# ControllerDiagrams.net
KiCad netlist of a schematic drawn in Altium Designer
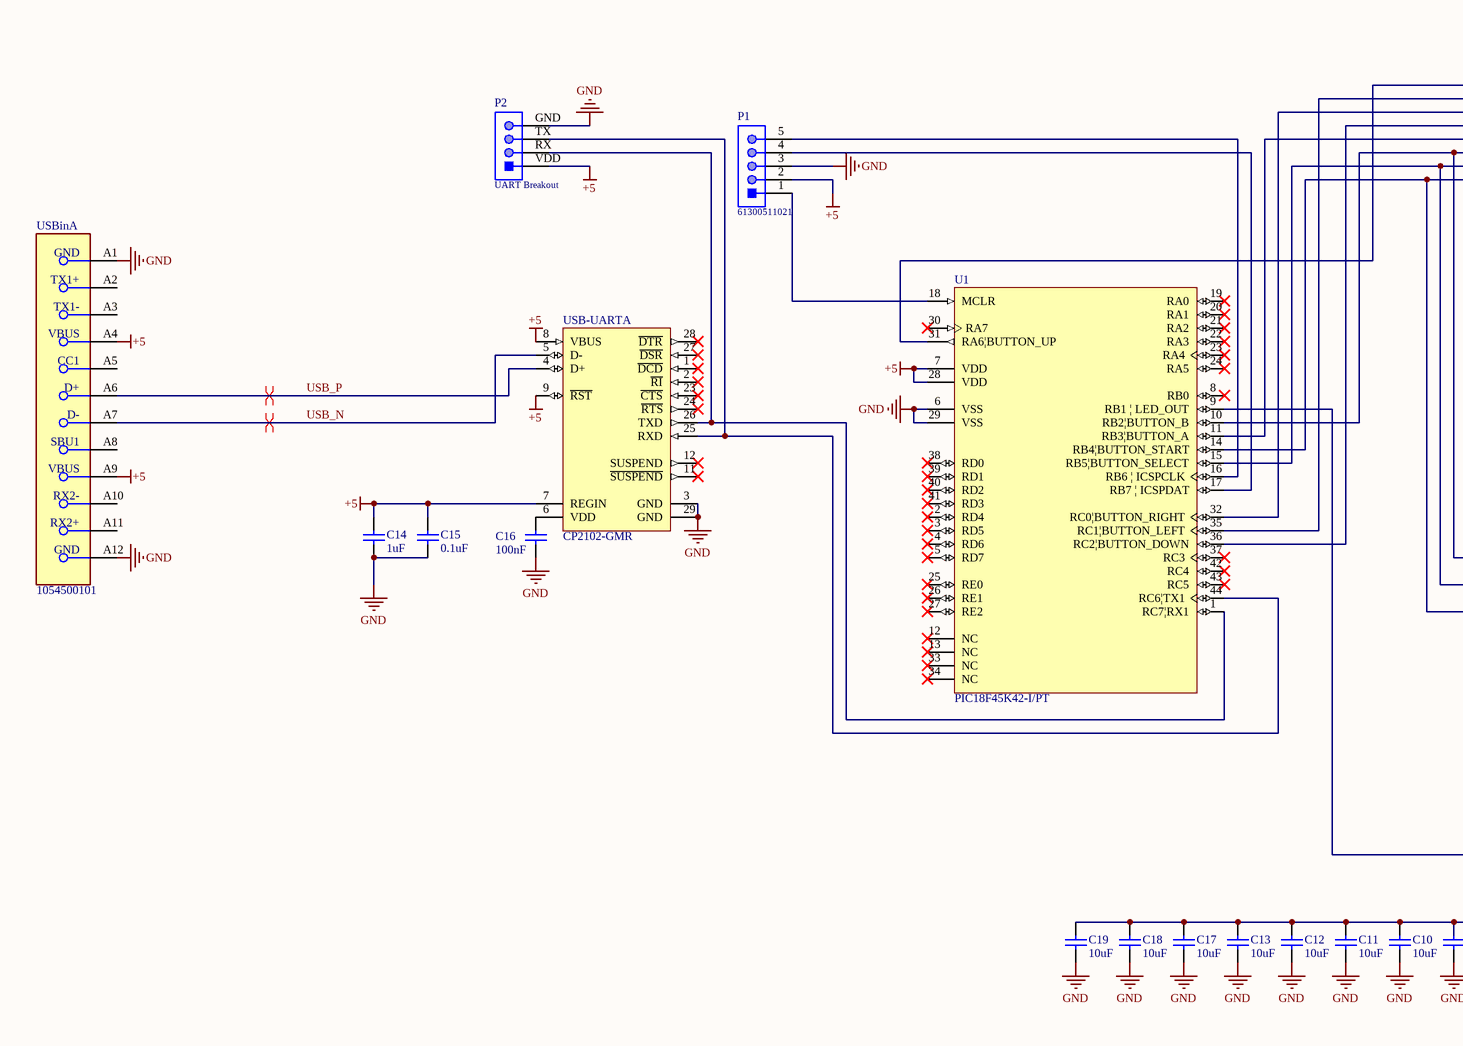
[diagram p0: ControllerDiagrams.SchDoc, left]
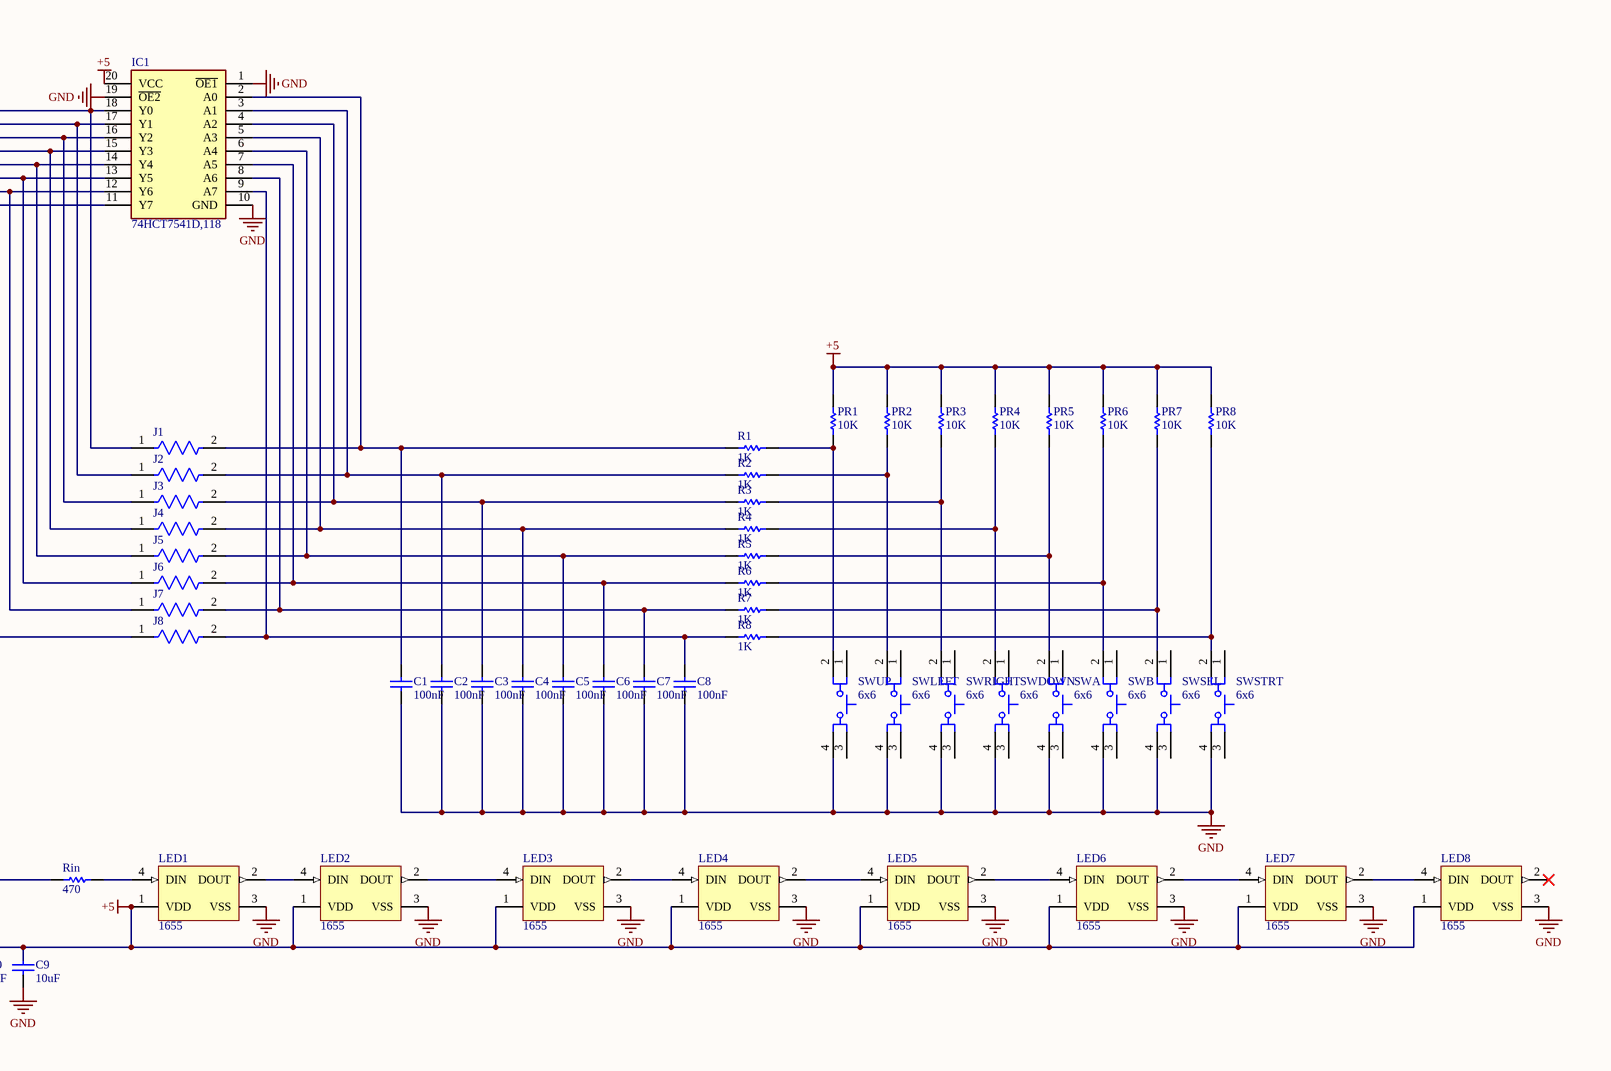
[diagram p1: ControllerDiagrams.SchDoc, right]

(export (version "E")
  (design (tool "Eeschema 10.0.6"))
  (components
    (comp (ref "C1")
      (value "100nF")
      (footprint "CAPC2013X140X50LL20T25")
      (description "Chip Capacitor, 2.2 uF, +/- 10%, 10 V, -55 to 85 degC, 0805 (2012 Metric), RoHS, Tape and Reel")
      (fields (field (name "MANUFACTURER") "AVX"))
      (libsource (lib "Altium Content Vault") (part "CAP-NP-2"))
    )
    (comp (ref "C2")
      (value "100nF")
      (footprint "CAPC2013X140X50LL20T25")
      (description "Chip Capacitor, 2.2 uF, +/- 10%, 10 V, -55 to 85 degC, 0805 (2012 Metric), RoHS, Tape and Reel")
      (fields (field (name "MANUFACTURER") "AVX"))
      (libsource (lib "Altium Content Vault") (part "CAP-NP-2"))
    )
    (comp (ref "C3")
      (value "100nF")
      (footprint "CAPC2013X140X50LL20T25")
      (description "Chip Capacitor, 2.2 uF, +/- 10%, 10 V, -55 to 85 degC, 0805 (2012 Metric), RoHS, Tape and Reel")
      (fields (field (name "MANUFACTURER") "AVX"))
      (libsource (lib "Altium Content Vault") (part "CAP-NP-2"))
    )
    (comp (ref "C4")
      (value "100nF")
      (footprint "CAPC2013X140X50LL20T25")
      (description "Chip Capacitor, 2.2 uF, +/- 10%, 10 V, -55 to 85 degC, 0805 (2012 Metric), RoHS, Tape and Reel")
      (fields (field (name "MANUFACTURER") "AVX"))
      (libsource (lib "Altium Content Vault") (part "CAP-NP-2"))
    )
    (comp (ref "C5")
      (value "100nF")
      (footprint "CAPC2013X140X50LL20T25")
      (description "Chip Capacitor, 2.2 uF, +/- 10%, 10 V, -55 to 85 degC, 0805 (2012 Metric), RoHS, Tape and Reel")
      (fields (field (name "MANUFACTURER") "AVX"))
      (libsource (lib "Altium Content Vault") (part "CAP-NP-2"))
    )
    (comp (ref "C6")
      (value "100nF")
      (footprint "CAPC2013X140X50LL20T25")
      (description "Chip Capacitor, 2.2 uF, +/- 10%, 10 V, -55 to 85 degC, 0805 (2012 Metric), RoHS, Tape and Reel")
      (fields (field (name "MANUFACTURER") "AVX"))
      (libsource (lib "Altium Content Vault") (part "CAP-NP-2"))
    )
    (comp (ref "C7")
      (value "100nF")
      (footprint "CAPC2013X140X50LL20T25")
      (description "Chip Capacitor, 2.2 uF, +/- 10%, 10 V, -55 to 85 degC, 0805 (2012 Metric), RoHS, Tape and Reel")
      (fields (field (name "MANUFACTURER") "AVX"))
      (libsource (lib "Altium Content Vault") (part "CAP-NP-2"))
    )
    (comp (ref "C8")
      (value "100nF")
      (footprint "CAPC2013X140X50LL20T25")
      (description "Chip Capacitor, 2.2 uF, +/- 10%, 10 V, -55 to 85 degC, 0805 (2012 Metric), RoHS, Tape and Reel")
      (fields (field (name "MANUFACTURER") "AVX"))
      (libsource (lib "Altium Content Vault") (part "CAP-NP-2"))
    )
    (comp (ref "C9")
      (value "10uF")
      (footprint "CAPC2013X140X50LL20T25")
      (description "Chip Capacitor, 2.2 uF, +/- 10%, 10 V, -55 to 85 degC, 0805 (2012 Metric), RoHS, Tape and Reel")
      (fields (field (name "MANUFACTURER") "AVX"))
      (libsource (lib "Altium Content Vault") (part "CAP-NP-2"))
    )
    (comp (ref "C10")
      (value "10uF")
      (footprint "CAPC2013X140X50LL20T25")
      (description "Chip Capacitor, 2.2 uF, +/- 10%, 10 V, -55 to 85 degC, 0805 (2012 Metric), RoHS, Tape and Reel")
      (fields (field (name "MANUFACTURER") "AVX"))
      (libsource (lib "Altium Content Vault") (part "CAP-NP-2"))
    )
    (comp (ref "C11")
      (value "10uF")
      (footprint "CAPC2013X140X50LL20T25")
      (description "Chip Capacitor, 2.2 uF, +/- 10%, 10 V, -55 to 85 degC, 0805 (2012 Metric), RoHS, Tape and Reel")
      (fields (field (name "MANUFACTURER") "AVX"))
      (libsource (lib "Altium Content Vault") (part "CAP-NP-2"))
    )
    (comp (ref "C12")
      (value "10uF")
      (footprint "CAPC2013X140X50LL20T25")
      (description "Chip Capacitor, 2.2 uF, +/- 10%, 10 V, -55 to 85 degC, 0805 (2012 Metric), RoHS, Tape and Reel")
      (fields (field (name "MANUFACTURER") "AVX"))
      (libsource (lib "Altium Content Vault") (part "CAP-NP-2"))
    )
    (comp (ref "C13")
      (value "10uF")
      (footprint "CAPC2013X140X50LL20T25")
      (description "Chip Capacitor, 2.2 uF, +/- 10%, 10 V, -55 to 85 degC, 0805 (2012 Metric), RoHS, Tape and Reel")
      (fields (field (name "MANUFACTURER") "AVX"))
      (libsource (lib "Altium Content Vault") (part "CAP-NP-2"))
    )
    (comp (ref "C14")
      (value "1uF")
      (footprint "CAPC2013X140X50LL20T25")
      (description "Chip Capacitor, 2.2 uF, +/- 10%, 10 V, -55 to 85 degC, 0805 (2012 Metric), RoHS, Tape and Reel")
      (fields (field (name "MANUFACTURER") "AVX"))
      (libsource (lib "Altium Content Vault") (part "CAP-NP-2"))
    )
    (comp (ref "C15")
      (value "0.1uF")
      (footprint "CAPC2013X140X50LL20T25")
      (description "Chip Capacitor, 2.2 uF, +/- 10%, 10 V, -55 to 85 degC, 0805 (2012 Metric), RoHS, Tape and Reel")
      (fields (field (name "MANUFACTURER") "AVX"))
      (libsource (lib "Altium Content Vault") (part "CAP-NP-2"))
    )
    (comp (ref "C16")
      (value "100nF")
      (footprint "CAPC2013X140X50LL20T25")
      (description "Chip Capacitor, 2.2 uF, +/- 10%, 10 V, -55 to 85 degC, 0805 (2012 Metric), RoHS, Tape and Reel")
      (fields (field (name "MANUFACTURER") "AVX"))
      (libsource (lib "Altium Content Vault") (part "CAP-NP-2"))
    )
    (comp (ref "C17")
      (value "10uF")
      (footprint "CAPC2013X140X50LL20T25")
      (description "Chip Capacitor, 2.2 uF, +/- 10%, 10 V, -55 to 85 degC, 0805 (2012 Metric), RoHS, Tape and Reel")
      (fields (field (name "MANUFACTURER") "AVX"))
      (libsource (lib "Altium Content Vault") (part "CAP-NP-2"))
    )
    (comp (ref "C18")
      (value "10uF")
      (footprint "CAPC2013X140X50LL20T25")
      (description "Chip Capacitor, 2.2 uF, +/- 10%, 10 V, -55 to 85 degC, 0805 (2012 Metric), RoHS, Tape and Reel")
      (fields (field (name "MANUFACTURER") "AVX"))
      (libsource (lib "Altium Content Vault") (part "CAP-NP-2"))
    )
    (comp (ref "C19")
      (value "10uF")
      (footprint "CAPC2013X140X50LL20T25")
      (description "Chip Capacitor, 2.2 uF, +/- 10%, 10 V, -55 to 85 degC, 0805 (2012 Metric), RoHS, Tape and Reel")
      (fields (field (name "MANUFACTURER") "AVX"))
      (libsource (lib "Altium Content Vault") (part "CAP-NP-2"))
    )
    (comp (ref "IC1")
      (value "74HCT7541D,118")
      (footprint "SamacSys:SOIC127P1032X265-20N")
      (description "Integrated Circuit")
      (fields (field (name "MOUSER PART NUMBER") "771-74HCT7541D-T"))
      (libsource (lib "*") (part "74HCT7541D,118"))
    )
    (comp (ref "J1")
      (value "~")
      (footprint "FP-ERJ-3GEY0R00V-MFG")
      (description "RES SMD 0 OHM JUMPER 1/10W 0603")
      (fields (field (name "TOLERANCE") "5%") (field (name "MANUFACTURER PART NUMBER") "ERJ-3GEY0R00V"))
      (libsource (lib "Altium Content Vault") (part "1029c3af85768c4190bb7ad29bc67b5"))
    )
    (comp (ref "J2")
      (value "~")
      (footprint "FP-ERJ-3GEY0R00V-MFG")
      (description "RES SMD 0 OHM JUMPER 1/10W 0603")
      (fields (field (name "TOLERANCE") "5%") (field (name "MANUFACTURER PART NUMBER") "ERJ-3GEY0R00V"))
      (libsource (lib "Altium Content Vault") (part "1029c3af85768c4190bb7ad29bc67b5"))
    )
    (comp (ref "J3")
      (value "~")
      (footprint "FP-ERJ-3GEY0R00V-MFG")
      (description "RES SMD 0 OHM JUMPER 1/10W 0603")
      (fields (field (name "TOLERANCE") "5%") (field (name "MANUFACTURER PART NUMBER") "ERJ-3GEY0R00V"))
      (libsource (lib "Altium Content Vault") (part "1029c3af85768c4190bb7ad29bc67b5"))
    )
    (comp (ref "J4")
      (value "~")
      (footprint "FP-ERJ-3GEY0R00V-MFG")
      (description "RES SMD 0 OHM JUMPER 1/10W 0603")
      (fields (field (name "TOLERANCE") "5%") (field (name "MANUFACTURER PART NUMBER") "ERJ-3GEY0R00V"))
      (libsource (lib "Altium Content Vault") (part "1029c3af85768c4190bb7ad29bc67b5"))
    )
    (comp (ref "J5")
      (value "~")
      (footprint "FP-ERJ-3GEY0R00V-MFG")
      (description "RES SMD 0 OHM JUMPER 1/10W 0603")
      (fields (field (name "TOLERANCE") "5%") (field (name "MANUFACTURER PART NUMBER") "ERJ-3GEY0R00V"))
      (libsource (lib "Altium Content Vault") (part "1029c3af85768c4190bb7ad29bc67b5"))
    )
    (comp (ref "J6")
      (value "~")
      (footprint "FP-ERJ-3GEY0R00V-MFG")
      (description "RES SMD 0 OHM JUMPER 1/10W 0603")
      (fields (field (name "TOLERANCE") "5%") (field (name "MANUFACTURER PART NUMBER") "ERJ-3GEY0R00V"))
      (libsource (lib "Altium Content Vault") (part "1029c3af85768c4190bb7ad29bc67b5"))
    )
    (comp (ref "J7")
      (value "~")
      (footprint "FP-ERJ-3GEY0R00V-MFG")
      (description "RES SMD 0 OHM JUMPER 1/10W 0603")
      (fields (field (name "TOLERANCE") "5%") (field (name "MANUFACTURER PART NUMBER") "ERJ-3GEY0R00V"))
      (libsource (lib "Altium Content Vault") (part "1029c3af85768c4190bb7ad29bc67b5"))
    )
    (comp (ref "J8")
      (value "~")
      (footprint "FP-ERJ-3GEY0R00V-MFG")
      (description "RES SMD 0 OHM JUMPER 1/10W 0603")
      (fields (field (name "TOLERANCE") "5%") (field (name "MANUFACTURER PART NUMBER") "ERJ-3GEY0R00V"))
      (libsource (lib "Altium Content Vault") (part "1029c3af85768c4190bb7ad29bc67b5"))
    )
    (comp (ref "LED1")
      (value "1655")
      (footprint "ADA-RGB-1655_V")
      (fields (field (name "MANUFACTURER") "Adafruit-Industries-LLC"))
      (libsource (lib "Altium Content Vault") (part "ADA-RGB-1655-4"))
    )
    (comp (ref "LED2")
      (value "1655")
      (footprint "ADA-RGB-1655_V")
      (fields (field (name "MANUFACTURER") "Adafruit-Industries-LLC"))
      (libsource (lib "Altium Content Vault") (part "ADA-RGB-1655-4"))
    )
    (comp (ref "LED3")
      (value "1655")
      (footprint "ADA-RGB-1655_V")
      (fields (field (name "MANUFACTURER") "Adafruit-Industries-LLC"))
      (libsource (lib "Altium Content Vault") (part "ADA-RGB-1655-4"))
    )
    (comp (ref "LED4")
      (value "1655")
      (footprint "ADA-RGB-1655_V")
      (fields (field (name "MANUFACTURER") "Adafruit-Industries-LLC"))
      (libsource (lib "Altium Content Vault") (part "ADA-RGB-1655-4"))
    )
    (comp (ref "LED5")
      (value "1655")
      (footprint "ADA-RGB-1655_V")
      (fields (field (name "MANUFACTURER") "Adafruit-Industries-LLC"))
      (libsource (lib "Altium Content Vault") (part "ADA-RGB-1655-4"))
    )
    (comp (ref "LED6")
      (value "1655")
      (footprint "ADA-RGB-1655_V")
      (fields (field (name "MANUFACTURER") "Adafruit-Industries-LLC"))
      (libsource (lib "Altium Content Vault") (part "ADA-RGB-1655-4"))
    )
    (comp (ref "LED7")
      (value "1655")
      (footprint "ADA-RGB-1655_V")
      (fields (field (name "MANUFACTURER") "Adafruit-Industries-LLC"))
      (libsource (lib "Altium Content Vault") (part "ADA-RGB-1655-4"))
    )
    (comp (ref "LED8")
      (value "1655")
      (footprint "ADA-RGB-1655_V")
      (fields (field (name "MANUFACTURER") "Adafruit-Industries-LLC"))
      (libsource (lib "Altium Content Vault") (part "ADA-RGB-1655-4"))
    )
    (comp (ref "P1")
      (value "61300511021")
      (footprint "61300511021")
      (description "THT Angled Pin Header WR-PHD, Pitch 2.54 mm, Single Row, 5 pins")
      (fields (field (name "MANUFACTURER") "Wurth Elektronik") (field (name "PUBLISHER") "WurthElektronik"))
      (libsource (lib "Altium Content Vault") (part "WE-CN-1P-M-R5"))
    )
    (comp (ref "P2")
      (value "UART Breakout")
      (footprint "61300411121")
      (description "THT Vertical Pin Header WR-PHD, Pitch 2.54 mm, Single Row, 4 pins")
      (fields
        (field (name "MANUFACTURER") "Wurth Elektronik")
        (field (name "PART NUMBER") "61300411121")
        (field (name "PUBLISHER") "WurthElektronik")
      )
      (libsource (lib "Altium Content Vault") (part "WE-CN-1P-M-R4"))
    )
    (comp (ref "PR1")
      (value "10K")
      (footprint "RESC2013X50X30LL20T20")
      (fields (field (name "MANUFACTURER") "Vishay Dale") (field (name "PART NUMBER") "CRCW08050000Z0EA"))
      (libsource (lib "Altium Content Vault") (part "RES"))
    )
    (comp (ref "PR2")
      (value "10K")
      (footprint "RESC2013X50X30LL20T20")
      (fields (field (name "MANUFACTURER") "Vishay Dale") (field (name "PART NUMBER") "CRCW08050000Z0EA"))
      (libsource (lib "Altium Content Vault") (part "RES"))
    )
    (comp (ref "PR3")
      (value "10K")
      (footprint "RESC2013X50X30LL20T20")
      (fields (field (name "MANUFACTURER") "Vishay Dale") (field (name "PART NUMBER") "CRCW08050000Z0EA"))
      (libsource (lib "Altium Content Vault") (part "RES"))
    )
    (comp (ref "PR4")
      (value "10K")
      (footprint "RESC2013X50X30LL20T20")
      (fields (field (name "MANUFACTURER") "Vishay Dale") (field (name "PART NUMBER") "CRCW08050000Z0EA"))
      (libsource (lib "Altium Content Vault") (part "RES"))
    )
    (comp (ref "PR5")
      (value "10K")
      (footprint "RESC2013X50X30LL20T20")
      (fields (field (name "MANUFACTURER") "Vishay Dale") (field (name "PART NUMBER") "CRCW08050000Z0EA"))
      (libsource (lib "Altium Content Vault") (part "RES"))
    )
    (comp (ref "PR6")
      (value "10K")
      (footprint "RESC2013X50X30LL20T20")
      (fields (field (name "MANUFACTURER") "Vishay Dale") (field (name "PART NUMBER") "CRCW08050000Z0EA"))
      (libsource (lib "Altium Content Vault") (part "RES"))
    )
    (comp (ref "PR7")
      (value "10K")
      (footprint "RESC2013X50X30LL20T20")
      (fields (field (name "MANUFACTURER") "Vishay Dale") (field (name "PART NUMBER") "CRCW08050000Z0EA"))
      (libsource (lib "Altium Content Vault") (part "RES"))
    )
    (comp (ref "PR8")
      (value "10K")
      (footprint "RESC2013X50X30LL20T20")
      (fields (field (name "MANUFACTURER") "Vishay Dale") (field (name "PART NUMBER") "CRCW08050000Z0EA"))
      (libsource (lib "Altium Content Vault") (part "RES"))
    )
    (comp (ref "R1")
      (value "1K")
      (footprint "RESC2013X50X30LL20T20")
      (fields (field (name "MANUFACTURER") "Vishay Dale") (field (name "PART NUMBER") "CRCW08050000Z0EA"))
      (libsource (lib "Altium Content Vault") (part "RES"))
    )
    (comp (ref "R2")
      (value "1K")
      (footprint "RESC2013X50X30LL20T20")
      (fields (field (name "MANUFACTURER") "Vishay Dale") (field (name "PART NUMBER") "CRCW08050000Z0EA"))
      (libsource (lib "Altium Content Vault") (part "RES"))
    )
    (comp (ref "R3")
      (value "1K")
      (footprint "RESC2013X50X30LL20T20")
      (fields (field (name "MANUFACTURER") "Vishay Dale") (field (name "PART NUMBER") "CRCW08050000Z0EA"))
      (libsource (lib "Altium Content Vault") (part "RES"))
    )
    (comp (ref "R4")
      (value "1K")
      (footprint "RESC2013X50X30LL20T20")
      (fields (field (name "MANUFACTURER") "Vishay Dale") (field (name "PART NUMBER") "CRCW08050000Z0EA"))
      (libsource (lib "Altium Content Vault") (part "RES"))
    )
    (comp (ref "R5")
      (value "1K")
      (footprint "RESC2013X50X30LL20T20")
      (fields (field (name "MANUFACTURER") "Vishay Dale") (field (name "PART NUMBER") "CRCW08050000Z0EA"))
      (libsource (lib "Altium Content Vault") (part "RES"))
    )
    (comp (ref "R6")
      (value "1K")
      (footprint "RESC2013X50X30LL20T20")
      (fields (field (name "MANUFACTURER") "Vishay Dale") (field (name "PART NUMBER") "CRCW08050000Z0EA"))
      (libsource (lib "Altium Content Vault") (part "RES"))
    )
    (comp (ref "R7")
      (value "1K")
      (footprint "RESC2013X50X30LL20T20")
      (fields (field (name "MANUFACTURER") "Vishay Dale") (field (name "PART NUMBER") "CRCW08050000Z0EA"))
      (libsource (lib "Altium Content Vault") (part "RES"))
    )
    (comp (ref "R8")
      (value "1K")
      (footprint "RESC2013X50X30LL20T20")
      (fields (field (name "MANUFACTURER") "Vishay Dale") (field (name "PART NUMBER") "CRCW08050000Z0EA"))
      (libsource (lib "Altium Content Vault") (part "RES"))
    )
    (comp (ref "Rin")
      (value "470")
      (footprint "RESC2013X50X30LL20T20")
      (fields (field (name "MANUFACTURER") "Vishay Dale") (field (name "PART NUMBER") "CRCW08050000Z0EA"))
      (libsource (lib "Altium Content Vault") (part "RES"))
    )
    (comp (ref "SWA")
      (value "6x6")
      (footprint "ESWI-TL1105SPF_V")
      (description "Tact Switch, SPST-NO, 50 mA, 12 VDC, -20 to 70 degC, 4-Pin THD, RoHS, Bulk")
      (fields (field (name "MANUFACTURER") "E-Switch"))
      (libsource (lib "Altium Content Vault") (part "SW-SPST-NO-4"))
    )
    (comp (ref "SWB")
      (value "6x6")
      (footprint "ESWI-TL1105SPF_V")
      (description "Tact Switch, SPST-NO, 50 mA, 12 VDC, -20 to 70 degC, 4-Pin THD, RoHS, Bulk")
      (fields (field (name "MANUFACTURER") "E-Switch"))
      (libsource (lib "Altium Content Vault") (part "SW-SPST-NO-4"))
    )
    (comp (ref "SWDOWN")
      (value "6x6")
      (footprint "ESWI-TL1105SPF_V")
      (description "Tact Switch, SPST-NO, 50 mA, 12 VDC, -20 to 70 degC, 4-Pin THD, RoHS, Bulk")
      (fields (field (name "MANUFACTURER") "E-Switch"))
      (libsource (lib "Altium Content Vault") (part "SW-SPST-NO-4"))
    )
    (comp (ref "SWLEFT")
      (value "6x6")
      (footprint "ESWI-TL1105SPF_V")
      (description "Tact Switch, SPST-NO, 50 mA, 12 VDC, -20 to 70 degC, 4-Pin THD, RoHS, Bulk")
      (fields (field (name "MANUFACTURER") "E-Switch"))
      (libsource (lib "Altium Content Vault") (part "SW-SPST-NO-4"))
    )
    (comp (ref "SWRIGHT")
      (value "6x6")
      (footprint "ESWI-TL1105SPF_V")
      (description "Tact Switch, SPST-NO, 50 mA, 12 VDC, -20 to 70 degC, 4-Pin THD, RoHS, Bulk")
      (fields (field (name "MANUFACTURER") "E-Switch"))
      (libsource (lib "Altium Content Vault") (part "SW-SPST-NO-4"))
    )
    (comp (ref "SWSEL")
      (value "6x6")
      (footprint "ESWI-TL1105SPF_V")
      (description "Tact Switch, SPST-NO, 50 mA, 12 VDC, -20 to 70 degC, 4-Pin THD, RoHS, Bulk")
      (fields (field (name "MANUFACTURER") "E-Switch"))
      (libsource (lib "Altium Content Vault") (part "SW-SPST-NO-4"))
    )
    (comp (ref "SWSTRT")
      (value "6x6")
      (footprint "ESWI-TL1105SPF_V")
      (description "Tact Switch, SPST-NO, 50 mA, 12 VDC, -20 to 70 degC, 4-Pin THD, RoHS, Bulk")
      (fields (field (name "MANUFACTURER") "E-Switch"))
      (libsource (lib "Altium Content Vault") (part "SW-SPST-NO-4"))
    )
    (comp (ref "SWUP")
      (value "6x6")
      (footprint "ESWI-TL1105SPF_V")
      (description "Tact Switch, SPST-NO, 50 mA, 12 VDC, -20 to 70 degC, 4-Pin THD, RoHS, Bulk")
      (fields (field (name "MANUFACTURER") "E-Switch"))
      (libsource (lib "Altium Content Vault") (part "SW-SPST-NO-4"))
    )
    (comp (ref "U1")
      (value "PIC18F45K42-I/PT")
      (footprint "TQFP-PT44_M")
      (libsource (lib "Altium Content Vault") (part "MC-8B-16F874A-SQ44B"))
    )
    (comp (ref "USB-UART")
      (value "CP2102-GMR")
      (footprint "SLAB-QFN-28-3125x3125TP_M")
      (description "Single-Chip USB to URAT Bridge, 3.3 V, -40 to 85 degC, 28-Pin QFN, RoHS, Tape and Reel")
      (fields (field (name "MANUFACTURER") "Silicon Labs"))
      (libsource (lib "Altium Content Vault") (part "SLAB-CP210X-QFN-28-29"))
    )
    (comp (ref "USBin")
      (value "1054500101")
      (footprint "FP-1054500101-MFG")
      (description "CONN RCP USB3.1 TYPEC 24P SMD RA")
      (fields
        (field (name "MANUFACTURER") "Molex")
        (field (name "OCTOPART") "https://octopart.com/105450-0101-molex-68082325")
      )
      (libsource (lib "Altium Content Vault") (part "9808b19ecaf079fb99eed69f0495cd0"))
    )
  )
  (nets
    (net (code "1") (name "+5") (class "Default")
      (node (ref "C10") (pin "2") (pinfunction "2_2") (pintype "passive"))
      (node (ref "C11") (pin "2") (pinfunction "2_2") (pintype "passive"))
      (node (ref "C12") (pin "2") (pinfunction "2_2") (pintype "passive"))
      (node (ref "C13") (pin "2") (pinfunction "2_2") (pintype "passive"))
      (node (ref "C14") (pin "2") (pinfunction "2_2") (pintype "passive"))
      (node (ref "C15") (pin "2") (pinfunction "2_2") (pintype "passive"))
      (node (ref "C17") (pin "2") (pinfunction "2_2") (pintype "passive"))
      (node (ref "C18") (pin "2") (pinfunction "2_2") (pintype "passive"))
      (node (ref "C19") (pin "2") (pinfunction "2_2") (pintype "passive"))
      (node (ref "C9") (pin "2") (pinfunction "2_2") (pintype "passive"))
      (node (ref "IC1") (pin "20") (pinfunction "VCC_20") (pintype "passive"))
      (node (ref "LED1") (pin "1") (pinfunction "VDD_1") (pintype "power_in"))
      (node (ref "LED2") (pin "1") (pinfunction "VDD_1") (pintype "power_in"))
      (node (ref "LED3") (pin "1") (pinfunction "VDD_1") (pintype "power_in"))
      (node (ref "LED4") (pin "1") (pinfunction "VDD_1") (pintype "power_in"))
      (node (ref "LED5") (pin "1") (pinfunction "VDD_1") (pintype "power_in"))
      (node (ref "LED6") (pin "1") (pinfunction "VDD_1") (pintype "power_in"))
      (node (ref "LED7") (pin "1") (pinfunction "VDD_1") (pintype "power_in"))
      (node (ref "LED8") (pin "1") (pinfunction "VDD_1") (pintype "power_in"))
      (node (ref "P1") (pin "2") (pinfunction "2_2") (pintype "passive"))
      (node (ref "P2") (pin "VDD") (pinfunction "1_VDD") (pintype "passive"))
      (node (ref "PR1") (pin "2") (pinfunction "2_2") (pintype "passive"))
      (node (ref "PR2") (pin "2") (pinfunction "2_2") (pintype "passive"))
      (node (ref "PR3") (pin "2") (pinfunction "2_2") (pintype "passive"))
      (node (ref "PR4") (pin "2") (pinfunction "2_2") (pintype "passive"))
      (node (ref "PR5") (pin "2") (pinfunction "2_2") (pintype "passive"))
      (node (ref "PR6") (pin "2") (pinfunction "2_2") (pintype "passive"))
      (node (ref "PR7") (pin "2") (pinfunction "2_2") (pintype "passive"))
      (node (ref "PR8") (pin "2") (pinfunction "2_2") (pintype "passive"))
      (node (ref "U1") (pin "28") (pinfunction "VDD_28") (pintype "power_in"))
      (node (ref "U1") (pin "7") (pinfunction "VDD_7") (pintype "power_in"))
      (node (ref "USB-UART") (pin "7") (pinfunction "REGIN_7") (pintype "power_in"))
      (node (ref "USB-UART") (pin "8") (pinfunction "VBUS_8") (pintype "input"))
      (node (ref "USB-UART") (pin "9") (pinfunction "~{RST}_9") (pintype "bidirectional"))
      (node (ref "USBin") (pin "A4") (pinfunction "VBUS_A4") (pintype "passive"))
      (node (ref "USBin") (pin "A9") (pinfunction "VBUS_A9") (pintype "passive"))
    )
    (net (code "2") (name "/USB_N") (class "Default")
      (node (ref "USB-UART") (pin "5") (pinfunction "D-_5") (pintype "bidirectional"))
      (node (ref "USBin") (pin "A7") (pinfunction "D-_A7") (pintype "passive"))
    )
    (net (code "3") (name "/USB_P") (class "Default")
      (node (ref "USB-UART") (pin "4") (pinfunction "D+_4") (pintype "bidirectional"))
      (node (ref "USBin") (pin "A6") (pinfunction "D+_A6") (pintype "passive"))
    )
    (net (code "4") (name "GND") (class "Default")
      (node (ref "C1") (pin "1") (pinfunction "1_1") (pintype "passive"))
      (node (ref "C10") (pin "1") (pinfunction "1_1") (pintype "passive"))
      (node (ref "C11") (pin "1") (pinfunction "1_1") (pintype "passive"))
      (node (ref "C12") (pin "1") (pinfunction "1_1") (pintype "passive"))
      (node (ref "C13") (pin "1") (pinfunction "1_1") (pintype "passive"))
      (node (ref "C14") (pin "1") (pinfunction "1_1") (pintype "passive"))
      (node (ref "C15") (pin "1") (pinfunction "1_1") (pintype "passive"))
      (node (ref "C16") (pin "2") (pinfunction "2_2") (pintype "passive"))
      (node (ref "C17") (pin "1") (pinfunction "1_1") (pintype "passive"))
      (node (ref "C18") (pin "1") (pinfunction "1_1") (pintype "passive"))
      (node (ref "C19") (pin "1") (pinfunction "1_1") (pintype "passive"))
      (node (ref "C2") (pin "1") (pinfunction "1_1") (pintype "passive"))
      (node (ref "C3") (pin "1") (pinfunction "1_1") (pintype "passive"))
      (node (ref "C4") (pin "1") (pinfunction "1_1") (pintype "passive"))
      (node (ref "C5") (pin "1") (pinfunction "1_1") (pintype "passive"))
      (node (ref "C6") (pin "1") (pinfunction "1_1") (pintype "passive"))
      (node (ref "C7") (pin "1") (pinfunction "1_1") (pintype "passive"))
      (node (ref "C8") (pin "1") (pinfunction "1_1") (pintype "passive"))
      (node (ref "C9") (pin "1") (pinfunction "1_1") (pintype "passive"))
      (node (ref "IC1") (pin "1") (pinfunction "~{OE1}_1") (pintype "passive"))
      (node (ref "IC1") (pin "10") (pinfunction "GND_10") (pintype "passive"))
      (node (ref "IC1") (pin "19") (pinfunction "~{OE2}_19") (pintype "passive"))
      (node (ref "LED1") (pin "3") (pinfunction "VSS_3") (pintype "power_in"))
      (node (ref "LED2") (pin "3") (pinfunction "VSS_3") (pintype "power_in"))
      (node (ref "LED3") (pin "3") (pinfunction "VSS_3") (pintype "power_in"))
      (node (ref "LED4") (pin "3") (pinfunction "VSS_3") (pintype "power_in"))
      (node (ref "LED5") (pin "3") (pinfunction "VSS_3") (pintype "power_in"))
      (node (ref "LED6") (pin "3") (pinfunction "VSS_3") (pintype "power_in"))
      (node (ref "LED7") (pin "3") (pinfunction "VSS_3") (pintype "power_in"))
      (node (ref "LED8") (pin "3") (pinfunction "VSS_3") (pintype "power_in"))
      (node (ref "P1") (pin "3") (pinfunction "3_3") (pintype "passive"))
      (node (ref "P2") (pin "GND") (pinfunction "4_GND") (pintype "passive"))
      (node (ref "SWA") (pin "4") (pinfunction "4_4") (pintype "passive"))
      (node (ref "SWB") (pin "4") (pinfunction "4_4") (pintype "passive"))
      (node (ref "SWDOWN") (pin "4") (pinfunction "4_4") (pintype "passive"))
      (node (ref "SWLEFT") (pin "4") (pinfunction "4_4") (pintype "passive"))
      (node (ref "SWRIGHT") (pin "4") (pinfunction "4_4") (pintype "passive"))
      (node (ref "SWSEL") (pin "4") (pinfunction "4_4") (pintype "passive"))
      (node (ref "SWSTRT") (pin "4") (pinfunction "4_4") (pintype "passive"))
      (node (ref "SWUP") (pin "4") (pinfunction "4_4") (pintype "passive"))
      (node (ref "U1") (pin "29") (pinfunction "VSS_29") (pintype "power_in"))
      (node (ref "U1") (pin "6") (pinfunction "VSS_6") (pintype "power_in"))
      (node (ref "USB-UART") (pin "29") (pinfunction "GND_29") (pintype "power_in"))
      (node (ref "USB-UART") (pin "3") (pinfunction "GND_3") (pintype "power_in"))
      (node (ref "USBin") (pin "A1") (pinfunction "GND_A1") (pintype "passive"))
      (node (ref "USBin") (pin "A12") (pinfunction "GND_A12") (pintype "passive"))
    )
    (net (code "5") (name "Net-(IC1-A0)") (class "Default")
      (node (ref "C1") (pin "2") (pinfunction "2_2") (pintype "passive"))
      (node (ref "IC1") (pin "2") (pinfunction "A0_2") (pintype "passive"))
      (node (ref "J1") (pin "2") (pinfunction "2_2") (pintype "passive"))
      (node (ref "R1") (pin "2") (pinfunction "2_2") (pintype "passive"))
    )
    (net (code "6") (name "Net-(IC1-A1)") (class "Default")
      (node (ref "C2") (pin "2") (pinfunction "2_2") (pintype "passive"))
      (node (ref "IC1") (pin "3") (pinfunction "A1_3") (pintype "passive"))
      (node (ref "J2") (pin "2") (pinfunction "2_2") (pintype "passive"))
      (node (ref "R2") (pin "2") (pinfunction "2_2") (pintype "passive"))
    )
    (net (code "7") (name "Net-(IC1-A2)") (class "Default")
      (node (ref "C3") (pin "2") (pinfunction "2_2") (pintype "passive"))
      (node (ref "IC1") (pin "4") (pinfunction "A2_4") (pintype "passive"))
      (node (ref "J3") (pin "2") (pinfunction "2_2") (pintype "passive"))
      (node (ref "R3") (pin "2") (pinfunction "2_2") (pintype "passive"))
    )
    (net (code "8") (name "Net-(IC1-A3)") (class "Default")
      (node (ref "C4") (pin "2") (pinfunction "2_2") (pintype "passive"))
      (node (ref "IC1") (pin "5") (pinfunction "A3_5") (pintype "passive"))
      (node (ref "J4") (pin "2") (pinfunction "2_2") (pintype "passive"))
      (node (ref "R4") (pin "2") (pinfunction "2_2") (pintype "passive"))
    )
    (net (code "9") (name "Net-(IC1-A4)") (class "Default")
      (node (ref "C5") (pin "2") (pinfunction "2_2") (pintype "passive"))
      (node (ref "IC1") (pin "6") (pinfunction "A4_6") (pintype "passive"))
      (node (ref "J5") (pin "2") (pinfunction "2_2") (pintype "passive"))
      (node (ref "R5") (pin "2") (pinfunction "2_2") (pintype "passive"))
    )
    (net (code "10") (name "Net-(IC1-A5)") (class "Default")
      (node (ref "C6") (pin "2") (pinfunction "2_2") (pintype "passive"))
      (node (ref "IC1") (pin "7") (pinfunction "A5_7") (pintype "passive"))
      (node (ref "J6") (pin "2") (pinfunction "2_2") (pintype "passive"))
      (node (ref "R6") (pin "2") (pinfunction "2_2") (pintype "passive"))
    )
    (net (code "11") (name "Net-(IC1-A6)") (class "Default")
      (node (ref "C7") (pin "2") (pinfunction "2_2") (pintype "passive"))
      (node (ref "IC1") (pin "8") (pinfunction "A6_8") (pintype "passive"))
      (node (ref "J7") (pin "2") (pinfunction "2_2") (pintype "passive"))
      (node (ref "R7") (pin "2") (pinfunction "2_2") (pintype "passive"))
    )
    (net (code "12") (name "Net-(IC1-A7)") (class "Default")
      (node (ref "C8") (pin "2") (pinfunction "2_2") (pintype "passive"))
      (node (ref "IC1") (pin "9") (pinfunction "A7_9") (pintype "passive"))
      (node (ref "J8") (pin "2") (pinfunction "2_2") (pintype "passive"))
      (node (ref "R8") (pin "2") (pinfunction "2_2") (pintype "passive"))
    )
    (net (code "13") (name "Net-(IC1-Y0)") (class "Default")
      (node (ref "IC1") (pin "18") (pinfunction "Y0_18") (pintype "passive"))
      (node (ref "J1") (pin "1") (pinfunction "1_1") (pintype "passive"))
      (node (ref "U1") (pin "31") (pinfunction "RA6¦BUTTON_UP_31") (pintype "output"))
    )
    (net (code "14") (name "Net-(IC1-Y1)") (class "Default")
      (node (ref "IC1") (pin "17") (pinfunction "Y1_17") (pintype "passive"))
      (node (ref "J2") (pin "1") (pinfunction "1_1") (pintype "passive"))
      (node (ref "U1") (pin "35") (pinfunction "RC1¦BUTTON_LEFT_35") (pintype "bidirectional"))
    )
    (net (code "15") (name "Net-(IC1-Y2)") (class "Default")
      (node (ref "IC1") (pin "16") (pinfunction "Y2_16") (pintype "passive"))
      (node (ref "J3") (pin "1") (pinfunction "1_1") (pintype "passive"))
      (node (ref "U1") (pin "32") (pinfunction "RC0¦BUTTON_RIGHT_32") (pintype "bidirectional"))
    )
    (net (code "16") (name "Net-(IC1-Y3)") (class "Default")
      (node (ref "IC1") (pin "15") (pinfunction "Y3_15") (pintype "passive"))
      (node (ref "J4") (pin "1") (pinfunction "1_1") (pintype "passive"))
      (node (ref "U1") (pin "36") (pinfunction "RC2¦BUTTON_DOWN_36") (pintype "bidirectional"))
    )
    (net (code "17") (name "Net-(IC1-Y4)") (class "Default")
      (node (ref "IC1") (pin "14") (pinfunction "Y4_14") (pintype "passive"))
      (node (ref "J5") (pin "1") (pinfunction "1_1") (pintype "passive"))
      (node (ref "U1") (pin "11") (pinfunction "RB3¦BUTTON_A_11") (pintype "bidirectional"))
    )
    (net (code "18") (name "Net-(IC1-Y5)") (class "Default")
      (node (ref "IC1") (pin "13") (pinfunction "Y5_13") (pintype "passive"))
      (node (ref "J6") (pin "1") (pinfunction "1_1") (pintype "passive"))
      (node (ref "U1") (pin "10") (pinfunction "RB2¦BUTTON_B_10") (pintype "bidirectional"))
    )
    (net (code "19") (name "Net-(IC1-Y6)") (class "Default")
      (node (ref "IC1") (pin "12") (pinfunction "Y6_12") (pintype "passive"))
      (node (ref "J7") (pin "1") (pinfunction "1_1") (pintype "passive"))
      (node (ref "U1") (pin "15") (pinfunction "RB5¦BUTTON_SELECT_15") (pintype "bidirectional"))
    )
    (net (code "20") (name "Net-(IC1-Y7)") (class "Default")
      (node (ref "IC1") (pin "11") (pinfunction "Y7_11") (pintype "passive"))
      (node (ref "J8") (pin "1") (pinfunction "1_1") (pintype "passive"))
      (node (ref "U1") (pin "14") (pinfunction "RB4¦BUTTON_START_14") (pintype "bidirectional"))
    )
    (net (code "21") (name "Net-(LED1-DIN)") (class "Default")
      (node (ref "LED1") (pin "4") (pinfunction "DIN_4") (pintype "input"))
      (node (ref "Rin") (pin "2") (pinfunction "2_2") (pintype "passive"))
    )
    (net (code "22") (name "Net-(LED1-DOUT)") (class "Default")
      (node (ref "LED1") (pin "2") (pinfunction "DOUT_2") (pintype "output"))
      (node (ref "LED2") (pin "4") (pinfunction "DIN_4") (pintype "input"))
    )
    (net (code "23") (name "Net-(LED2-DOUT)") (class "Default")
      (node (ref "LED2") (pin "2") (pinfunction "DOUT_2") (pintype "output"))
      (node (ref "LED3") (pin "4") (pinfunction "DIN_4") (pintype "input"))
    )
    (net (code "24") (name "Net-(LED3-DOUT)") (class "Default")
      (node (ref "LED3") (pin "2") (pinfunction "DOUT_2") (pintype "output"))
      (node (ref "LED4") (pin "4") (pinfunction "DIN_4") (pintype "input"))
    )
    (net (code "25") (name "Net-(LED4-DOUT)") (class "Default")
      (node (ref "LED4") (pin "2") (pinfunction "DOUT_2") (pintype "output"))
      (node (ref "LED5") (pin "4") (pinfunction "DIN_4") (pintype "input"))
    )
    (net (code "26") (name "Net-(LED5-DOUT)") (class "Default")
      (node (ref "LED5") (pin "2") (pinfunction "DOUT_2") (pintype "output"))
      (node (ref "LED6") (pin "4") (pinfunction "DIN_4") (pintype "input"))
    )
    (net (code "27") (name "Net-(LED6-DOUT)") (class "Default")
      (node (ref "LED6") (pin "2") (pinfunction "DOUT_2") (pintype "output"))
      (node (ref "LED7") (pin "4") (pinfunction "DIN_4") (pintype "input"))
    )
    (net (code "28") (name "Net-(LED7-DOUT)") (class "Default")
      (node (ref "LED7") (pin "2") (pinfunction "DOUT_2") (pintype "output"))
      (node (ref "LED8") (pin "4") (pinfunction "DIN_4") (pintype "input"))
    )
    (net (code "29") (name "Net-(P2-2)") (class "Default")
      (node (ref "P2") (pin "RX") (pinfunction "2_RX") (pintype "passive"))
      (node (ref "U1") (pin "1") (pinfunction "RC7¦RX1_1") (pintype "bidirectional"))
      (node (ref "USB-UART") (pin "26") (pinfunction "TXD_26") (pintype "output"))
    )
    (net (code "30") (name "Net-(P2-3)") (class "Default")
      (node (ref "P2") (pin "TX") (pinfunction "3_TX") (pintype "passive"))
      (node (ref "U1") (pin "44") (pinfunction "RC6¦TX1_44") (pintype "bidirectional"))
      (node (ref "USB-UART") (pin "25") (pinfunction "RXD_25") (pintype "input"))
    )
    (net (code "31") (name "Net-(PR1-Pad1)") (class "Default")
      (node (ref "PR1") (pin "1") (pinfunction "1_1") (pintype "passive"))
      (node (ref "R1") (pin "1") (pinfunction "1_1") (pintype "passive"))
      (node (ref "SWUP") (pin "2") (pinfunction "2_2") (pintype "passive"))
    )
    (net (code "32") (name "Net-(PR2-Pad1)") (class "Default")
      (node (ref "PR2") (pin "1") (pinfunction "1_1") (pintype "passive"))
      (node (ref "R2") (pin "1") (pinfunction "1_1") (pintype "passive"))
      (node (ref "SWLEFT") (pin "2") (pinfunction "2_2") (pintype "passive"))
    )
    (net (code "33") (name "Net-(PR3-Pad1)") (class "Default")
      (node (ref "PR3") (pin "1") (pinfunction "1_1") (pintype "passive"))
      (node (ref "R3") (pin "1") (pinfunction "1_1") (pintype "passive"))
      (node (ref "SWRIGHT") (pin "2") (pinfunction "2_2") (pintype "passive"))
    )
    (net (code "34") (name "Net-(PR4-Pad1)") (class "Default")
      (node (ref "PR4") (pin "1") (pinfunction "1_1") (pintype "passive"))
      (node (ref "R4") (pin "1") (pinfunction "1_1") (pintype "passive"))
      (node (ref "SWDOWN") (pin "2") (pinfunction "2_2") (pintype "passive"))
    )
    (net (code "35") (name "Net-(PR5-Pad1)") (class "Default")
      (node (ref "PR5") (pin "1") (pinfunction "1_1") (pintype "passive"))
      (node (ref "R5") (pin "1") (pinfunction "1_1") (pintype "passive"))
      (node (ref "SWA") (pin "2") (pinfunction "2_2") (pintype "passive"))
    )
    (net (code "36") (name "Net-(PR6-Pad1)") (class "Default")
      (node (ref "PR6") (pin "1") (pinfunction "1_1") (pintype "passive"))
      (node (ref "R6") (pin "1") (pinfunction "1_1") (pintype "passive"))
      (node (ref "SWB") (pin "2") (pinfunction "2_2") (pintype "passive"))
    )
    (net (code "37") (name "Net-(PR7-Pad1)") (class "Default")
      (node (ref "PR7") (pin "1") (pinfunction "1_1") (pintype "passive"))
      (node (ref "R7") (pin "1") (pinfunction "1_1") (pintype "passive"))
      (node (ref "SWSEL") (pin "2") (pinfunction "2_2") (pintype "passive"))
    )
    (net (code "38") (name "Net-(PR8-Pad1)") (class "Default")
      (node (ref "PR8") (pin "1") (pinfunction "1_1") (pintype "passive"))
      (node (ref "R8") (pin "1") (pinfunction "1_1") (pintype "passive"))
      (node (ref "SWSTRT") (pin "2") (pinfunction "2_2") (pintype "passive"))
    )
    (net (code "39") (name "Net-(U1-MCLR)") (class "Default")
      (node (ref "P1") (pin "1") (pinfunction "1_1") (pintype "passive"))
      (node (ref "U1") (pin "18") (pinfunction "MCLR_18") (pintype "input"))
    )
    (net (code "40") (name "Net-(U1-RB1_¦_LED_OUT)") (class "Default")
      (node (ref "Rin") (pin "1") (pinfunction "1_1") (pintype "passive"))
      (node (ref "U1") (pin "9") (pinfunction "RB1_¦_LED_OUT_9") (pintype "bidirectional"))
    )
    (net (code "41") (name "Net-(U1-RB6_¦_ICSPCLK)") (class "Default")
      (node (ref "P1") (pin "5") (pinfunction "5_5") (pintype "passive"))
      (node (ref "U1") (pin "16") (pinfunction "RB6_¦_ICSPCLK_16") (pintype "bidirectional"))
    )
    (net (code "42") (name "Net-(U1-RB7_¦_ICSPDAT)") (class "Default")
      (node (ref "P1") (pin "4") (pinfunction "4_4") (pintype "passive"))
      (node (ref "U1") (pin "17") (pinfunction "RB7_¦_ICSPDAT_17") (pintype "bidirectional"))
    )
    (net (code "43") (name "Net-(USB-UARTA-VDD)") (class "Default")
      (node (ref "C16") (pin "1") (pinfunction "1_1") (pintype "passive"))
      (node (ref "USB-UART") (pin "6") (pinfunction "VDD_6") (pintype "power_in"))
    )
    (net (code "44") (name "unconnected-(LED8-DOUT-Pad2)") (class "Default")
      (node (ref "LED8") (pin "2") (pinfunction "DOUT_2") (pintype "output+no_connect"))
    )
    (net (code "45") (name "unconnected-(SWA-Pad1)") (class "Default")
      (node (ref "SWA") (pin "1") (pinfunction "1_1") (pintype "passive"))
    )
    (net (code "46") (name "unconnected-(SWA-Pad3)") (class "Default")
      (node (ref "SWA") (pin "3") (pinfunction "3_3") (pintype "passive"))
    )
    (net (code "47") (name "unconnected-(SWB-Pad1)") (class "Default")
      (node (ref "SWB") (pin "1") (pinfunction "1_1") (pintype "passive"))
    )
    (net (code "48") (name "unconnected-(SWB-Pad3)") (class "Default")
      (node (ref "SWB") (pin "3") (pinfunction "3_3") (pintype "passive"))
    )
    (net (code "49") (name "unconnected-(SWDOWN-Pad1)") (class "Default")
      (node (ref "SWDOWN") (pin "1") (pinfunction "1_1") (pintype "passive"))
    )
    (net (code "50") (name "unconnected-(SWDOWN-Pad3)") (class "Default")
      (node (ref "SWDOWN") (pin "3") (pinfunction "3_3") (pintype "passive"))
    )
    (net (code "51") (name "unconnected-(SWLEFT-Pad1)") (class "Default")
      (node (ref "SWLEFT") (pin "1") (pinfunction "1_1") (pintype "passive"))
    )
    (net (code "52") (name "unconnected-(SWLEFT-Pad3)") (class "Default")
      (node (ref "SWLEFT") (pin "3") (pinfunction "3_3") (pintype "passive"))
    )
    (net (code "53") (name "unconnected-(SWRIGHT-Pad1)") (class "Default")
      (node (ref "SWRIGHT") (pin "1") (pinfunction "1_1") (pintype "passive"))
    )
    (net (code "54") (name "unconnected-(SWRIGHT-Pad3)") (class "Default")
      (node (ref "SWRIGHT") (pin "3") (pinfunction "3_3") (pintype "passive"))
    )
    (net (code "55") (name "unconnected-(SWSEL-Pad1)") (class "Default")
      (node (ref "SWSEL") (pin "1") (pinfunction "1_1") (pintype "passive"))
    )
    (net (code "56") (name "unconnected-(SWSEL-Pad3)") (class "Default")
      (node (ref "SWSEL") (pin "3") (pinfunction "3_3") (pintype "passive"))
    )
    (net (code "57") (name "unconnected-(SWSTRT-Pad1)") (class "Default")
      (node (ref "SWSTRT") (pin "1") (pinfunction "1_1") (pintype "passive"))
    )
    (net (code "58") (name "unconnected-(SWSTRT-Pad3)") (class "Default")
      (node (ref "SWSTRT") (pin "3") (pinfunction "3_3") (pintype "passive"))
    )
    (net (code "59") (name "unconnected-(SWUP-Pad1)") (class "Default")
      (node (ref "SWUP") (pin "1") (pinfunction "1_1") (pintype "passive"))
    )
    (net (code "60") (name "unconnected-(SWUP-Pad3)") (class "Default")
      (node (ref "SWUP") (pin "3") (pinfunction "3_3") (pintype "passive"))
    )
    (net (code "61") (name "unconnected-(U1-NC-Pad12)") (class "Default")
      (node (ref "U1") (pin "12") (pinfunction "NC_12") (pintype "passive+no_connect"))
    )
    (net (code "62") (name "unconnected-(U1-NC-Pad13)") (class "Default")
      (node (ref "U1") (pin "13") (pinfunction "NC_13") (pintype "passive+no_connect"))
    )
    (net (code "63") (name "unconnected-(U1-NC-Pad33)") (class "Default")
      (node (ref "U1") (pin "33") (pinfunction "NC_33") (pintype "passive+no_connect"))
    )
    (net (code "64") (name "unconnected-(U1-NC-Pad34)") (class "Default")
      (node (ref "U1") (pin "34") (pinfunction "NC_34") (pintype "passive+no_connect"))
    )
    (net (code "65") (name "unconnected-(U1-RA0-Pad19)") (class "Default")
      (node (ref "U1") (pin "19") (pinfunction "RA0_19") (pintype "bidirectional+no_connect"))
    )
    (net (code "66") (name "unconnected-(U1-RA1-Pad20)") (class "Default")
      (node (ref "U1") (pin "20") (pinfunction "RA1_20") (pintype "bidirectional+no_connect"))
    )
    (net (code "67") (name "unconnected-(U1-RA2-Pad21)") (class "Default")
      (node (ref "U1") (pin "21") (pinfunction "RA2_21") (pintype "bidirectional+no_connect"))
    )
    (net (code "68") (name "unconnected-(U1-RA3-Pad22)") (class "Default")
      (node (ref "U1") (pin "22") (pinfunction "RA3_22") (pintype "bidirectional+no_connect"))
    )
    (net (code "69") (name "unconnected-(U1-RA4-Pad23)") (class "Default")
      (node (ref "U1") (pin "23") (pinfunction "RA4_23") (pintype "bidirectional+no_connect"))
    )
    (net (code "70") (name "unconnected-(U1-RA5-Pad24)") (class "Default")
      (node (ref "U1") (pin "24") (pinfunction "RA5_24") (pintype "bidirectional+no_connect"))
    )
    (net (code "71") (name "unconnected-(U1-RA7-Pad30)") (class "Default")
      (node (ref "U1") (pin "30") (pinfunction "RA7_30") (pintype "input+no_connect"))
    )
    (net (code "72") (name "unconnected-(U1-RB0-Pad8)") (class "Default")
      (node (ref "U1") (pin "8") (pinfunction "RB0_8") (pintype "bidirectional+no_connect"))
    )
    (net (code "73") (name "unconnected-(U1-RC3-Pad37)") (class "Default")
      (node (ref "U1") (pin "37") (pinfunction "RC3_37") (pintype "bidirectional+no_connect"))
    )
    (net (code "74") (name "unconnected-(U1-RC4-Pad42)") (class "Default")
      (node (ref "U1") (pin "42") (pinfunction "RC4_42") (pintype "bidirectional+no_connect"))
    )
    (net (code "75") (name "unconnected-(U1-RC5-Pad43)") (class "Default")
      (node (ref "U1") (pin "43") (pinfunction "RC5_43") (pintype "bidirectional+no_connect"))
    )
    (net (code "76") (name "unconnected-(U1-RD0-Pad38)") (class "Default")
      (node (ref "U1") (pin "38") (pinfunction "RD0_38") (pintype "bidirectional+no_connect"))
    )
    (net (code "77") (name "unconnected-(U1-RD1-Pad39)") (class "Default")
      (node (ref "U1") (pin "39") (pinfunction "RD1_39") (pintype "bidirectional+no_connect"))
    )
    (net (code "78") (name "unconnected-(U1-RD2-Pad40)") (class "Default")
      (node (ref "U1") (pin "40") (pinfunction "RD2_40") (pintype "bidirectional+no_connect"))
    )
    (net (code "79") (name "unconnected-(U1-RD3-Pad41)") (class "Default")
      (node (ref "U1") (pin "41") (pinfunction "RD3_41") (pintype "bidirectional+no_connect"))
    )
    (net (code "80") (name "unconnected-(U1-RD4-Pad2)") (class "Default")
      (node (ref "U1") (pin "2") (pinfunction "RD4_2") (pintype "bidirectional+no_connect"))
    )
    (net (code "81") (name "unconnected-(U1-RD5-Pad3)") (class "Default")
      (node (ref "U1") (pin "3") (pinfunction "RD5_3") (pintype "bidirectional+no_connect"))
    )
    (net (code "82") (name "unconnected-(U1-RD6-Pad4)") (class "Default")
      (node (ref "U1") (pin "4") (pinfunction "RD6_4") (pintype "bidirectional+no_connect"))
    )
    (net (code "83") (name "unconnected-(U1-RD7-Pad5)") (class "Default")
      (node (ref "U1") (pin "5") (pinfunction "RD7_5") (pintype "bidirectional+no_connect"))
    )
    (net (code "84") (name "unconnected-(U1-RE0-Pad25)") (class "Default")
      (node (ref "U1") (pin "25") (pinfunction "RE0_25") (pintype "bidirectional+no_connect"))
    )
    (net (code "85") (name "unconnected-(U1-RE1-Pad26)") (class "Default")
      (node (ref "U1") (pin "26") (pinfunction "RE1_26") (pintype "bidirectional+no_connect"))
    )
    (net (code "86") (name "unconnected-(U1-RE2-Pad27)") (class "Default")
      (node (ref "U1") (pin "27") (pinfunction "RE2_27") (pintype "bidirectional+no_connect"))
    )
    (net (code "87") (name "unconnected-(USB-UARTA-SUSPEND-Pad12)") (class "Default")
      (node (ref "USB-UART") (pin "12") (pinfunction "SUSPEND_12") (pintype "output+no_connect"))
    )
    (net (code "88") (name "unconnected-(USB-UARTA-~{CTS}-Pad23)") (class "Default")
      (node (ref "USB-UART") (pin "23") (pinfunction "~{CTS}_23") (pintype "input+no_connect"))
    )
    (net (code "89") (name "unconnected-(USB-UARTA-~{DCD}-Pad1)") (class "Default")
      (node (ref "USB-UART") (pin "1") (pinfunction "~{DCD}_1") (pintype "input+no_connect"))
    )
    (net (code "90") (name "unconnected-(USB-UARTA-~{DSR}-Pad27)") (class "Default")
      (node (ref "USB-UART") (pin "27") (pinfunction "~{DSR}_27") (pintype "input+no_connect"))
    )
    (net (code "91") (name "unconnected-(USB-UARTA-~{DTR}-Pad28)") (class "Default")
      (node (ref "USB-UART") (pin "28") (pinfunction "~{DTR}_28") (pintype "output+no_connect"))
    )
    (net (code "92") (name "unconnected-(USB-UARTA-~{RI}-Pad2)") (class "Default")
      (node (ref "USB-UART") (pin "2") (pinfunction "~{RI}_2") (pintype "input+no_connect"))
    )
    (net (code "93") (name "unconnected-(USB-UARTA-~{RTS}-Pad24)") (class "Default")
      (node (ref "USB-UART") (pin "24") (pinfunction "~{RTS}_24") (pintype "output+no_connect"))
    )
    (net (code "94") (name "unconnected-(USB-UARTA-~{SUSPEND}-Pad11)") (class "Default")
      (node (ref "USB-UART") (pin "11") (pinfunction "~{SUSPEND}_11") (pintype "output+no_connect"))
    )
    (net (code "95") (name "unconnected-(USBinA-CC1-PadA5)") (class "Default")
      (node (ref "USBin") (pin "A5") (pinfunction "CC1_A5") (pintype "passive"))
    )
    (net (code "96") (name "unconnected-(USBinA-RX2+-PadA11)") (class "Default")
      (node (ref "USBin") (pin "A11") (pinfunction "RX2+_A11") (pintype "passive"))
    )
    (net (code "97") (name "unconnected-(USBinA-RX2--PadA10)") (class "Default")
      (node (ref "USBin") (pin "A10") (pinfunction "RX2-_A10") (pintype "passive"))
    )
    (net (code "98") (name "unconnected-(USBinA-SBU1-PadA8)") (class "Default")
      (node (ref "USBin") (pin "A8") (pinfunction "SBU1_A8") (pintype "passive"))
    )
    (net (code "99") (name "unconnected-(USBinA-TX1+-PadA2)") (class "Default")
      (node (ref "USBin") (pin "A2") (pinfunction "TX1+_A2") (pintype "passive"))
    )
    (net (code "100") (name "unconnected-(USBinA-TX1--PadA3)") (class "Default")
      (node (ref "USBin") (pin "A3") (pinfunction "TX1-_A3") (pintype "passive"))
    )
  )
)
